# module.net
KiCad netlist of a schematic drawn in EAGLE
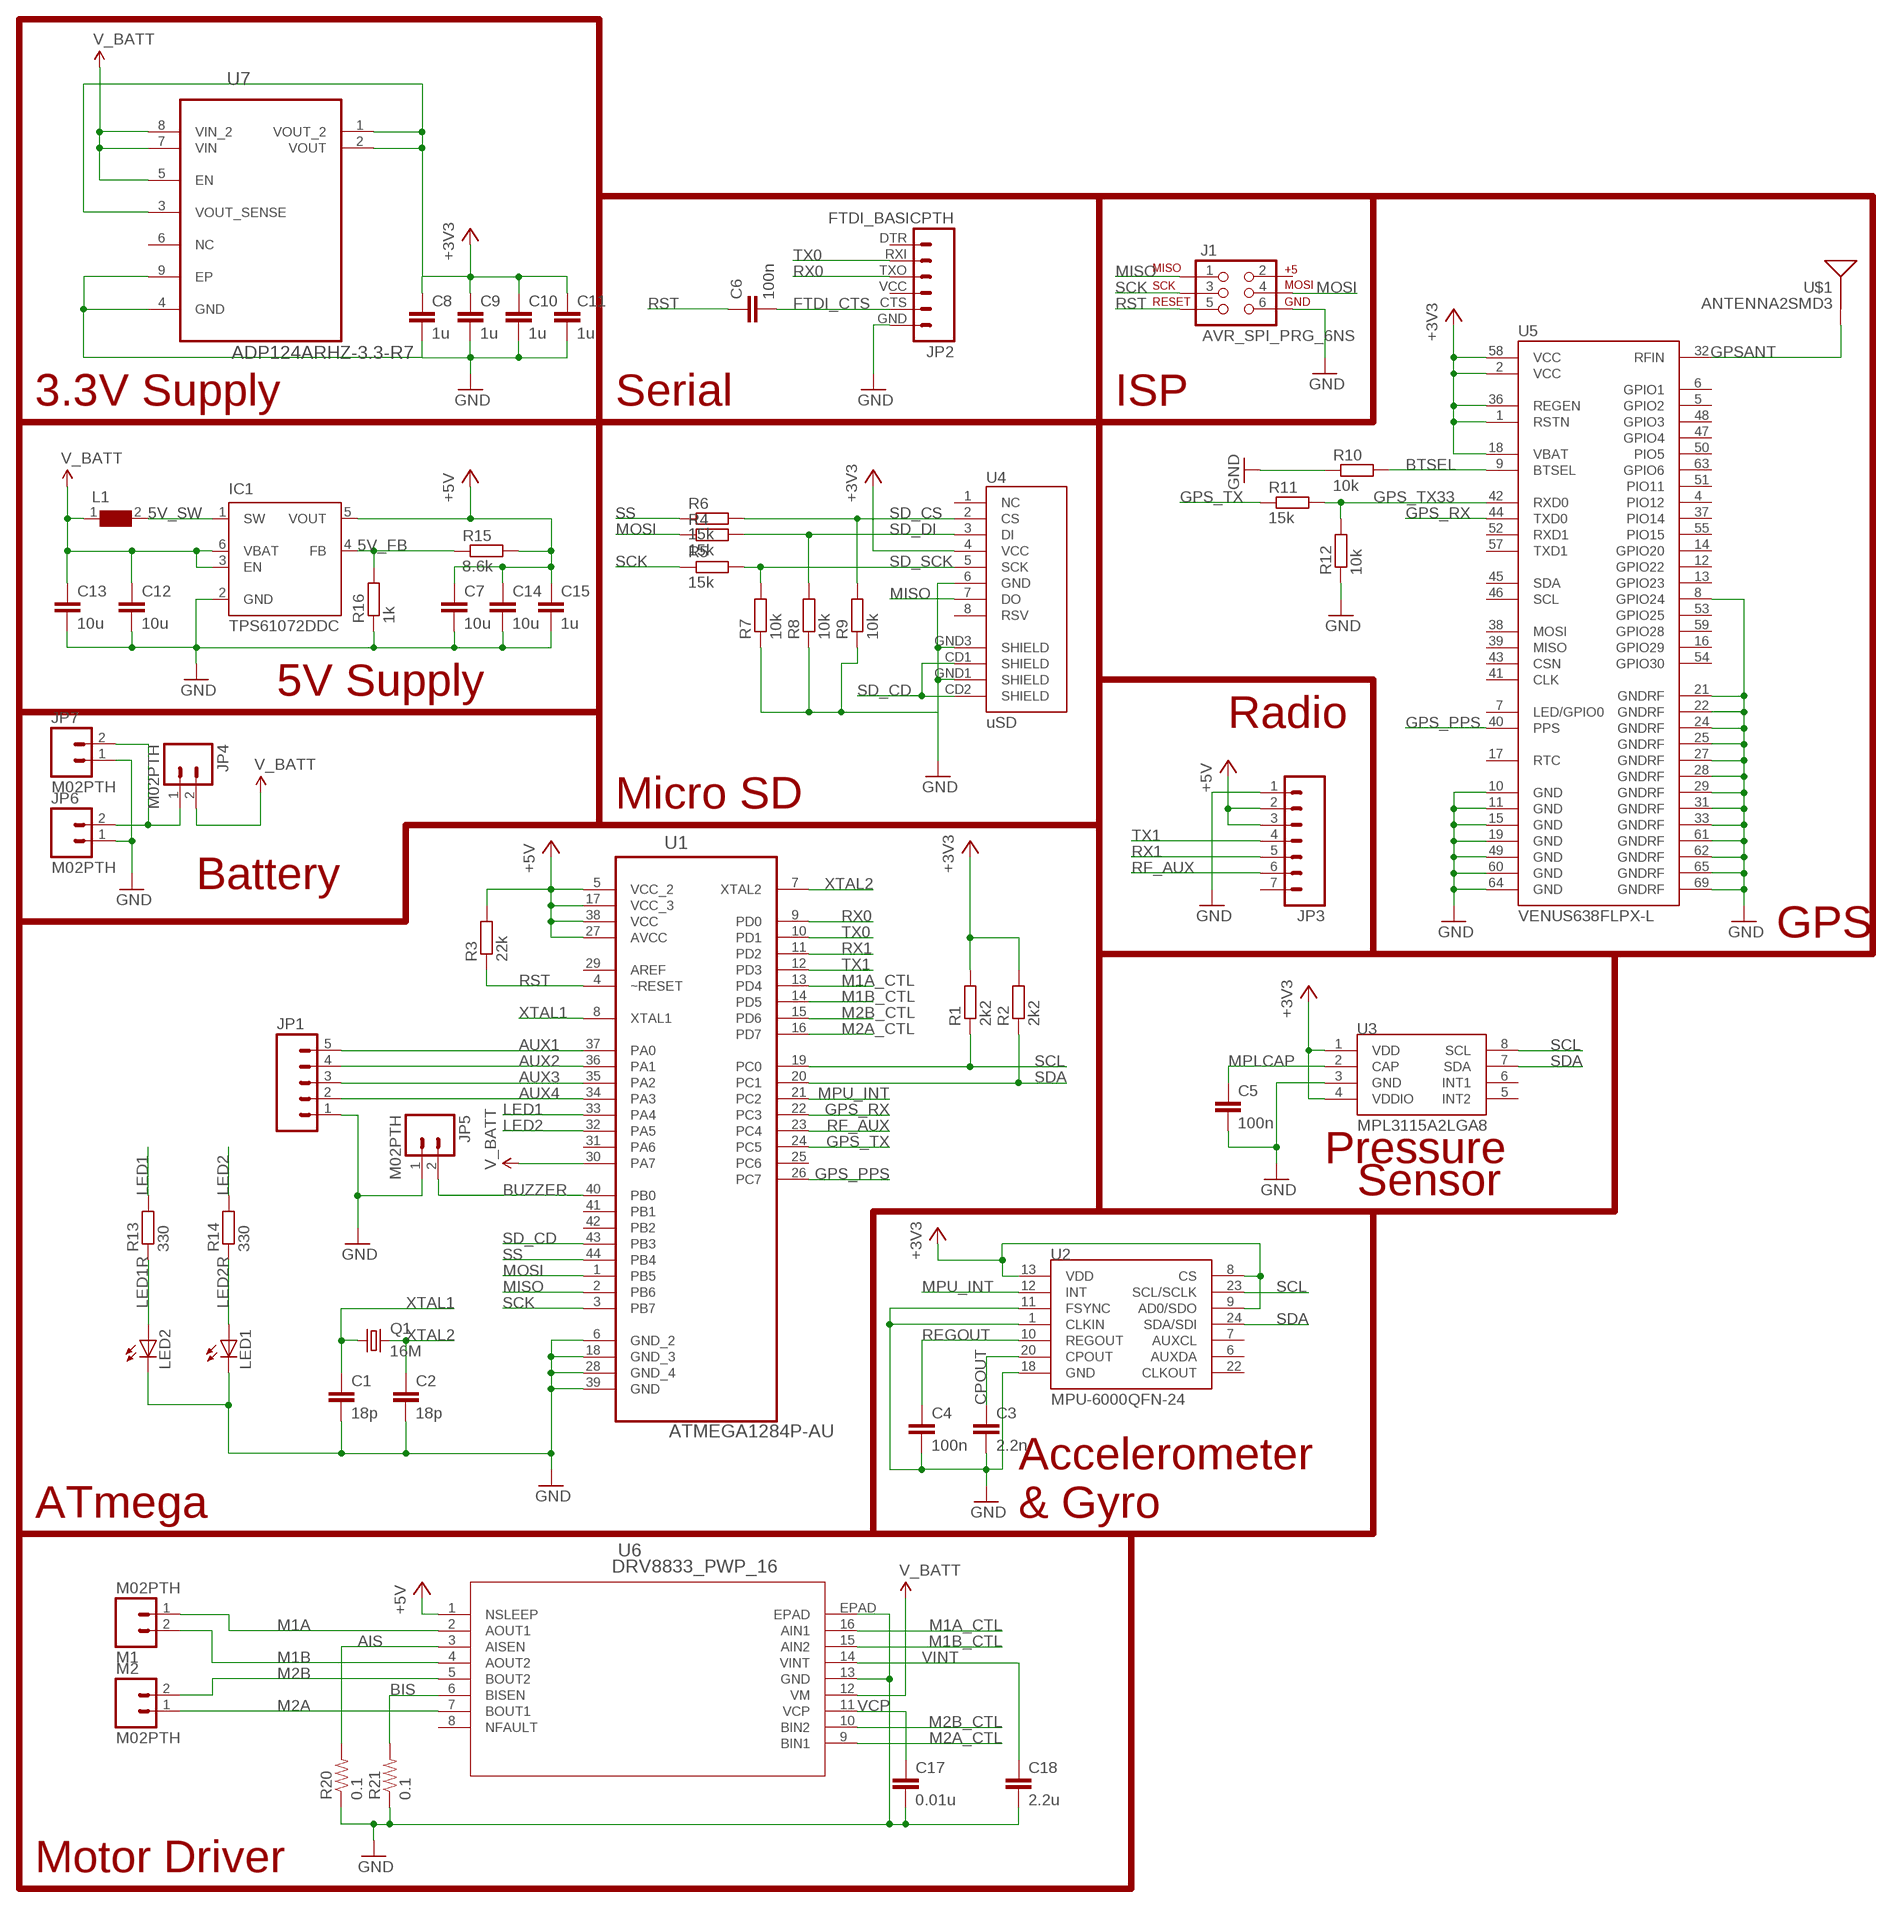
[diagram p0: schematic, sheet 1]

(export (version "E")
  (design (tool "Eeschema 10.0.6"))
  (components
    (comp (ref "C1")
      (value "18p")
      (footprint "eagle-import:C0805")
      (libsource (lib "eagle-import") (part "C-EUC0805"))
    )
    (comp (ref "C2")
      (value "18p")
      (footprint "eagle-import:C0805")
      (libsource (lib "eagle-import") (part "C-EUC0805"))
    )
    (comp (ref "C3")
      (value "2.2n")
      (footprint "eagle-import:C0805")
      (libsource (lib "eagle-import") (part "C-EUC0805"))
    )
    (comp (ref "C4")
      (value "100n")
      (footprint "eagle-import:C0805")
      (libsource (lib "eagle-import") (part "C-EUC0805"))
    )
    (comp (ref "C5")
      (value "100n")
      (footprint "eagle-import:C0805")
      (libsource (lib "eagle-import") (part "C-EUC0805"))
    )
    (comp (ref "C6")
      (value "100n")
      (footprint "eagle-import:C0805")
      (libsource (lib "eagle-import") (part "C-EUC0805"))
    )
    (comp (ref "C7")
      (value "10u")
      (footprint "eagle-import:C0805")
      (libsource (lib "eagle-import") (part "C-EUC0805"))
    )
    (comp (ref "C8")
      (value "1u")
      (footprint "eagle-import:C0603")
      (libsource (lib "eagle-import") (part "C-EUC0603"))
    )
    (comp (ref "C9")
      (value "1u")
      (footprint "eagle-import:C0603")
      (libsource (lib "eagle-import") (part "C-EUC0603"))
    )
    (comp (ref "C10")
      (value "1u")
      (footprint "eagle-import:C0603")
      (libsource (lib "eagle-import") (part "C-EUC0603"))
    )
    (comp (ref "C11")
      (value "1u")
      (footprint "eagle-import:C0603")
      (libsource (lib "eagle-import") (part "C-EUC0603"))
    )
    (comp (ref "C12")
      (value "10u")
      (footprint "eagle-import:C0805")
      (libsource (lib "eagle-import") (part "C-EUC0805"))
    )
    (comp (ref "C13")
      (value "10u")
      (footprint "eagle-import:C0805")
      (libsource (lib "eagle-import") (part "C-EUC0805"))
    )
    (comp (ref "C14")
      (value "10u")
      (footprint "eagle-import:C0805")
      (libsource (lib "eagle-import") (part "C-EUC0805"))
    )
    (comp (ref "C15")
      (value "1u")
      (footprint "eagle-import:C0805")
      (libsource (lib "eagle-import") (part "C-EUC0805"))
    )
    (comp (ref "C17")
      (value "0.01u")
      (footprint "eagle-import:0805")
      (libsource (lib "eagle-import") (part "CAP0805"))
    )
    (comp (ref "C18")
      (value "2.2u")
      (footprint "eagle-import:0805")
      (libsource (lib "eagle-import") (part "CAP0805"))
    )
    (comp (ref "IC1")
      (value "TPS61072DDC")
      (footprint "eagle-import:TSOT23-6_DDC")
      (fields (field (name "MPN") "TPS61072DDCR"))
      (libsource (lib "eagle-import") (part "TPS6107DDC2"))
    )
    (comp (ref "J1")
      (value "AVR_SPI_PRG_6NS")
      (footprint "eagle-import:2X3-NS")
      (libsource (lib "eagle-import") (part "AVR_SPI_PRG_6NS"))
    )
    (comp (ref "JP1")
      (value "M05PTH")
      (footprint "eagle-import:1X05")
      (libsource (lib "eagle-import") (part "M05PTH"))
    )
    (comp (ref "JP2")
      (value "FTDI_BASICPTH")
      (footprint "eagle-import:FTDI_BASIC")
      (libsource (lib "eagle-import") (part "FTDI_BASICPTH"))
    )
    (comp (ref "JP3")
      (value "M07")
      (footprint "eagle-import:1X07")
      (libsource (lib "eagle-import") (part "M07"))
    )
    (comp (ref "JP4")
      (value "M02PTH")
      (footprint "eagle-import:1X02")
      (libsource (lib "eagle-import") (part "M02PTH"))
    )
    (comp (ref "JP5")
      (value "M02PTH")
      (footprint "eagle-import:1X02")
      (libsource (lib "eagle-import") (part "M02PTH"))
    )
    (comp (ref "JP6")
      (value "M02PTH")
      (footprint "eagle-import:1X02")
      (libsource (lib "eagle-import") (part "M02PTH"))
    )
    (comp (ref "JP7")
      (value "M02PTH")
      (footprint "eagle-import:1X02")
      (libsource (lib "eagle-import") (part "M02PTH"))
    )
    (comp (ref "L1")
      (value "WE-TPC-744031004_3816")
      (footprint "eagle-import:WE-TPC_3816")
      (fields (field (name "MPN") "744031004 "))
      (libsource (lib "eagle-import") (part "WE-TPC_3816-744031004"))
    )
    (comp (ref "LED1")
      (value "LEDCHIPLED_0805")
      (footprint "eagle-import:CHIPLED_0805")
      (libsource (lib "eagle-import") (part "LEDCHIPLED_0805"))
    )
    (comp (ref "LED2")
      (value "LEDCHIPLED_0805")
      (footprint "eagle-import:CHIPLED_0805")
      (libsource (lib "eagle-import") (part "LEDCHIPLED_0805"))
    )
    (comp (ref "M1")
      (value "M02PTH")
      (footprint "eagle-import:1X02")
      (libsource (lib "eagle-import") (part "M02PTH"))
    )
    (comp (ref "M2")
      (value "M02PTH")
      (footprint "eagle-import:1X02")
      (libsource (lib "eagle-import") (part "M02PTH"))
    )
    (comp (ref "Q1")
      (value "16M")
      (footprint "eagle-import:HC49UP")
      (libsource (lib "eagle-import") (part "CRYSTALHC49UP"))
    )
    (comp (ref "R1")
      (value "2k2")
      (footprint "eagle-import:R0805")
      (libsource (lib "eagle-import") (part "R-EU_R0805"))
    )
    (comp (ref "R2")
      (value "2k2")
      (footprint "eagle-import:R0805")
      (libsource (lib "eagle-import") (part "R-EU_R0805"))
    )
    (comp (ref "R3")
      (value "22k")
      (footprint "eagle-import:R0805")
      (libsource (lib "eagle-import") (part "R-EU_R0805"))
    )
    (comp (ref "R4")
      (value "15k")
      (footprint "eagle-import:R0805")
      (libsource (lib "eagle-import") (part "R-EU_R0805"))
    )
    (comp (ref "R5")
      (value "15k")
      (footprint "eagle-import:R0805")
      (libsource (lib "eagle-import") (part "R-EU_R0805"))
    )
    (comp (ref "R6")
      (value "15k")
      (footprint "eagle-import:R0805")
      (libsource (lib "eagle-import") (part "R-EU_R0805"))
    )
    (comp (ref "R7")
      (value "10k")
      (footprint "eagle-import:R0805")
      (libsource (lib "eagle-import") (part "R-EU_R0805"))
    )
    (comp (ref "R8")
      (value "10k")
      (footprint "eagle-import:R0805")
      (libsource (lib "eagle-import") (part "R-EU_R0805"))
    )
    (comp (ref "R9")
      (value "10k")
      (footprint "eagle-import:R0805")
      (libsource (lib "eagle-import") (part "R-EU_R0805"))
    )
    (comp (ref "R10")
      (value "10k")
      (footprint "eagle-import:R0805")
      (libsource (lib "eagle-import") (part "R-EU_R0805"))
    )
    (comp (ref "R11")
      (value "15k")
      (footprint "eagle-import:R0805")
      (libsource (lib "eagle-import") (part "R-EU_R0805"))
    )
    (comp (ref "R12")
      (value "10k")
      (footprint "eagle-import:R0805")
      (libsource (lib "eagle-import") (part "R-EU_R0805"))
    )
    (comp (ref "R13")
      (value "330")
      (footprint "eagle-import:R0805")
      (libsource (lib "eagle-import") (part "R-EU_R0805"))
    )
    (comp (ref "R14")
      (value "330")
      (footprint "eagle-import:R0805")
      (libsource (lib "eagle-import") (part "R-EU_R0805"))
    )
    (comp (ref "R15")
      (value "8.6k")
      (footprint "eagle-import:R0805")
      (libsource (lib "eagle-import") (part "R-EU_R0805"))
    )
    (comp (ref "R16")
      (value "1k")
      (footprint "eagle-import:R0805")
      (libsource (lib "eagle-import") (part "R-EU_R0805"))
    )
    (comp (ref "R20")
      (value "0.1")
      (footprint "eagle-import:1206")
      (libsource (lib "eagle-import") (part "RESISTOR1206"))
    )
    (comp (ref "R21")
      (value "0.1")
      (footprint "eagle-import:1206")
      (libsource (lib "eagle-import") (part "RESISTOR1206"))
    )
    (comp (ref "U$1")
      (value "ANTENNA2SMD3")
      (footprint "eagle-import:ANTENNA-CHIP4")
      (libsource (lib "eagle-import") (part "ANTENNA2SMD3"))
    )
    (comp (ref "U1")
      (value "ATMEGA1284P-AU")
      (footprint "eagle-import:QFP80P1200X1200X120-44N")
      (libsource (lib "eagle-import") (part "ATMEGA1284P-AU"))
    )
    (comp (ref "U2")
      (value "MPU-6000QFN-24")
      (footprint "eagle-import:QFN-24-TESTING")
      (libsource (lib "eagle-import") (part "MPU-6000QFN-24"))
    )
    (comp (ref "U3")
      (value "MPL3115A2LGA8")
      (footprint "eagle-import:LGA8")
      (libsource (lib "eagle-import") (part "MPL3115A2LGA8"))
    )
    (comp (ref "U4")
      (value "uSD")
      (footprint "eagle-import:MICRO-SD-SOCKET-PP")
      (libsource (lib "eagle-import") (part "USD-SOCKETNEW"))
    )
    (comp (ref "U5")
      (value "VENUS638FLPX-L")
      (footprint "eagle-import:VENUS638FLPX")
      (libsource (lib "eagle-import") (part "VENUS638FLPX-L"))
    )
    (comp (ref "U6")
      (value "DRV8833_PWP_16")
      (footprint "eagle-import:PWP16_2P31X2P46")
      (fields
        (field (name "GENERIC_PART_NUMBER") "DRV8833")
        (field (name "MANUFACTURER") "Texas Instruments")
        (field (name "MANUFACTURER_PART_NUMBER") "drv8833_pwp_16")
      )
      (libsource (lib "eagle-import") (part "DRV8833_PWP_16"))
    )
    (comp (ref "U7")
      (value "ADP124ARHZ-3.3-R7")
      (footprint "eagle-import:SOP65P490X110-9N")
      (libsource (lib "eagle-import") (part "ADP124ARHZ-3.3-R7"))
    )
  )
  (nets
    (net (code "1") (name "+3V3") (class "Default")
      (node (ref "C10") (pin "1") (pinfunction "1_1") (pintype "passive"))
      (node (ref "C11") (pin "1") (pinfunction "1_1") (pintype "passive"))
      (node (ref "C8") (pin "1") (pinfunction "1_1") (pintype "passive"))
      (node (ref "C9") (pin "1") (pinfunction "1_1") (pintype "passive"))
      (node (ref "R1") (pin "2") (pinfunction "2_2") (pintype "passive"))
      (node (ref "R2") (pin "2") (pinfunction "2_2") (pintype "passive"))
      (node (ref "U2") (pin "13") (pinfunction "VDD_13") (pintype "bidirectional"))
      (node (ref "U2") (pin "8") (pinfunction "CS_8") (pintype "bidirectional"))
      (node (ref "U2") (pin "9") (pinfunction "AD0/SDO_9") (pintype "bidirectional"))
      (node (ref "U3") (pin "1") (pinfunction "VDD_1") (pintype "bidirectional"))
      (node (ref "U3") (pin "4") (pinfunction "VDDIO_4") (pintype "bidirectional"))
      (node (ref "U4") (pin "4") (pinfunction "VCC_4") (pintype "bidirectional"))
      (node (ref "U5") (pin "1") (pinfunction "RSTN_1") (pintype "bidirectional"))
      (node (ref "U5") (pin "18") (pinfunction "VBAT_18") (pintype "bidirectional"))
      (node (ref "U5") (pin "2") (pinfunction "VCC_2") (pintype "bidirectional"))
      (node (ref "U5") (pin "36") (pinfunction "REGEN_36") (pintype "bidirectional"))
      (node (ref "U5") (pin "58") (pinfunction "VCC_58") (pintype "bidirectional"))
      (node (ref "U7") (pin "1") (pinfunction "VOUT_2_1") (pintype "output"))
      (node (ref "U7") (pin "2") (pinfunction "VOUT_2") (pintype "output"))
      (node (ref "U7") (pin "3") (pinfunction "VOUT_SENSE_3") (pintype "input"))
    )
    (net (code "2") (name "+5V") (class "Default")
      (node (ref "C14") (pin "1") (pinfunction "1_1") (pintype "passive"))
      (node (ref "C15") (pin "1") (pinfunction "1_1") (pintype "passive"))
      (node (ref "C7") (pin "1") (pinfunction "1_1") (pintype "passive"))
      (node (ref "IC1") (pin "5") (pinfunction "VOUT_5") (pintype "passive"))
      (node (ref "JP3") (pin "2") (pinfunction "2_2") (pintype "passive"))
      (node (ref "JP3") (pin "3") (pinfunction "3_3") (pintype "passive"))
      (node (ref "R15") (pin "2") (pinfunction "2_2") (pintype "passive"))
      (node (ref "R3") (pin "2") (pinfunction "2_2") (pintype "passive"))
      (node (ref "U1") (pin "17") (pinfunction "VCC_3_17") (pintype "power_in"))
      (node (ref "U1") (pin "27") (pinfunction "AVCC_27") (pintype "power_in"))
      (node (ref "U1") (pin "38") (pinfunction "VCC_38") (pintype "power_in"))
      (node (ref "U1") (pin "5") (pinfunction "VCC_2_5") (pintype "power_in"))
      (node (ref "U6") (pin "1") (pinfunction "NSLEEP_1") (pintype "input"))
    )
    (net (code "3") (name "/5V_FB") (class "Default")
      (node (ref "IC1") (pin "4") (pinfunction "FB_4") (pintype "input"))
      (node (ref "R15") (pin "1") (pinfunction "1_1") (pintype "passive"))
      (node (ref "R16") (pin "2") (pinfunction "2_2") (pintype "passive"))
    )
    (net (code "4") (name "/5V_SW") (class "Default")
      (node (ref "IC1") (pin "1") (pinfunction "SW_1") (pintype "input"))
      (node (ref "L1") (pin "2") (pinfunction "2_2") (pintype "passive"))
    )
    (net (code "5") (name "/AIS") (class "Default")
      (node (ref "R20") (pin "2") (pinfunction "2_2") (pintype "passive"))
      (node (ref "U6") (pin "3") (pinfunction "AISEN_3") (pintype "bidirectional"))
    )
    (net (code "6") (name "/AUX1") (class "Default")
      (node (ref "JP1") (pin "5") (pinfunction "5_5") (pintype "passive"))
      (node (ref "U1") (pin "37") (pinfunction "PA0_37") (pintype "bidirectional"))
    )
    (net (code "7") (name "/AUX2") (class "Default")
      (node (ref "JP1") (pin "4") (pinfunction "4_4") (pintype "passive"))
      (node (ref "U1") (pin "36") (pinfunction "PA1_36") (pintype "bidirectional"))
    )
    (net (code "8") (name "/AUX3") (class "Default")
      (node (ref "JP1") (pin "3") (pinfunction "3_3") (pintype "passive"))
      (node (ref "U1") (pin "35") (pinfunction "PA2_35") (pintype "bidirectional"))
    )
    (net (code "9") (name "/AUX4") (class "Default")
      (node (ref "JP1") (pin "2") (pinfunction "2_2") (pintype "passive"))
      (node (ref "U1") (pin "34") (pinfunction "PA3_34") (pintype "bidirectional"))
    )
    (net (code "10") (name "/BIS") (class "Default")
      (node (ref "R21") (pin "2") (pinfunction "2_2") (pintype "passive"))
      (node (ref "U6") (pin "6") (pinfunction "BISEN_6") (pintype "bidirectional"))
    )
    (net (code "11") (name "/BTSEL") (class "Default")
      (node (ref "R10") (pin "2") (pinfunction "2_2") (pintype "passive"))
      (node (ref "U5") (pin "9") (pinfunction "BTSEL_9") (pintype "bidirectional"))
    )
    (net (code "12") (name "/BUZZER") (class "Default")
      (node (ref "JP5") (pin "2") (pinfunction "2_2") (pintype "passive"))
      (node (ref "U1") (pin "40") (pinfunction "PB0_40") (pintype "bidirectional"))
    )
    (net (code "13") (name "/CPOUT") (class "Default")
      (node (ref "C3") (pin "1") (pinfunction "1_1") (pintype "passive"))
      (node (ref "U2") (pin "20") (pinfunction "CPOUT_20") (pintype "bidirectional"))
    )
    (net (code "14") (name "/FTDI_CTS") (class "Default")
      (node (ref "C6") (pin "2") (pinfunction "2_2") (pintype "passive"))
      (node (ref "JP2") (pin "CTS") (pinfunction "5_CTS") (pintype "passive"))
    )
    (net (code "15") (name "/GPSANT") (class "Default")
      (node (ref "U$1") (pin "SIG") (pinfunction "SIGNAL_SIG") (pintype "bidirectional"))
      (node (ref "U5") (pin "32") (pinfunction "RFIN_32") (pintype "bidirectional"))
    )
    (net (code "16") (name "/GPS_PPS") (class "Default")
      (node (ref "U1") (pin "26") (pinfunction "PC7_26") (pintype "bidirectional"))
      (node (ref "U5") (pin "40") (pinfunction "PPS_40") (pintype "bidirectional"))
    )
    (net (code "17") (name "/GPS_RX") (class "Default")
      (node (ref "U1") (pin "22") (pinfunction "PC3_22") (pintype "bidirectional"))
      (node (ref "U5") (pin "44") (pinfunction "TXD0_44") (pintype "bidirectional"))
    )
    (net (code "18") (name "/GPS_TX") (class "Default")
      (node (ref "R11") (pin "1") (pinfunction "1_1") (pintype "passive"))
      (node (ref "U1") (pin "24") (pinfunction "PC5_24") (pintype "bidirectional"))
    )
    (net (code "19") (name "/GPS_TX33") (class "Default")
      (node (ref "R11") (pin "2") (pinfunction "2_2") (pintype "passive"))
      (node (ref "R12") (pin "2") (pinfunction "2_2") (pintype "passive"))
      (node (ref "U5") (pin "42") (pinfunction "RXD0_42") (pintype "bidirectional"))
    )
    (net (code "20") (name "/LED1") (class "Default")
      (node (ref "R13") (pin "2") (pinfunction "2_2") (pintype "passive"))
      (node (ref "U1") (pin "33") (pinfunction "PA4_33") (pintype "bidirectional"))
    )
    (net (code "21") (name "/LED1R") (class "Default")
      (node (ref "LED2") (pin "A") (pinfunction "A_A") (pintype "passive"))
      (node (ref "R13") (pin "1") (pinfunction "1_1") (pintype "passive"))
    )
    (net (code "22") (name "/LED2") (class "Default")
      (node (ref "R14") (pin "2") (pinfunction "2_2") (pintype "passive"))
      (node (ref "U1") (pin "32") (pinfunction "PA5_32") (pintype "bidirectional"))
    )
    (net (code "23") (name "/LED2R") (class "Default")
      (node (ref "LED1") (pin "A") (pinfunction "A_A") (pintype "passive"))
      (node (ref "R14") (pin "1") (pinfunction "1_1") (pintype "passive"))
    )
    (net (code "24") (name "/M1A") (class "Default")
      (node (ref "M1") (pin "1") (pinfunction "1_1") (pintype "passive"))
      (node (ref "U6") (pin "2") (pinfunction "AOUT1_2") (pintype "output"))
    )
    (net (code "25") (name "/M1A_CTL") (class "Default")
      (node (ref "U1") (pin "13") (pinfunction "PD4_13") (pintype "bidirectional"))
      (node (ref "U6") (pin "16") (pinfunction "AIN1_16") (pintype "input"))
    )
    (net (code "26") (name "/M1B") (class "Default")
      (node (ref "M1") (pin "2") (pinfunction "2_2") (pintype "passive"))
      (node (ref "U6") (pin "4") (pinfunction "AOUT2_4") (pintype "output"))
    )
    (net (code "27") (name "/M1B_CTL") (class "Default")
      (node (ref "U1") (pin "14") (pinfunction "PD5_14") (pintype "bidirectional"))
      (node (ref "U6") (pin "15") (pinfunction "AIN2_15") (pintype "input"))
    )
    (net (code "28") (name "/M2A") (class "Default")
      (node (ref "M2") (pin "1") (pinfunction "1_1") (pintype "passive"))
      (node (ref "U6") (pin "7") (pinfunction "BOUT1_7") (pintype "output"))
    )
    (net (code "29") (name "/M2A_CTL") (class "Default")
      (node (ref "U1") (pin "16") (pinfunction "PD7_16") (pintype "bidirectional"))
      (node (ref "U6") (pin "9") (pinfunction "BIN1_9") (pintype "input"))
    )
    (net (code "30") (name "/M2B") (class "Default")
      (node (ref "M2") (pin "2") (pinfunction "2_2") (pintype "passive"))
      (node (ref "U6") (pin "5") (pinfunction "BOUT2_5") (pintype "output"))
    )
    (net (code "31") (name "/M2B_CTL") (class "Default")
      (node (ref "U1") (pin "15") (pinfunction "PD6_15") (pintype "bidirectional"))
      (node (ref "U6") (pin "10") (pinfunction "BIN2_10") (pintype "input"))
    )
    (net (code "32") (name "/MISO") (class "Default")
      (node (ref "J1") (pin "1") (pinfunction "1_1") (pintype "passive"))
      (node (ref "U1") (pin "2") (pinfunction "PB6_2") (pintype "bidirectional"))
      (node (ref "U4") (pin "7") (pinfunction "DO_7") (pintype "bidirectional"))
    )
    (net (code "33") (name "/MOSI") (class "Default")
      (node (ref "J1") (pin "4") (pinfunction "4_4") (pintype "passive"))
      (node (ref "R4") (pin "1") (pinfunction "1_1") (pintype "passive"))
      (node (ref "U1") (pin "1") (pinfunction "PB5_1") (pintype "bidirectional"))
    )
    (net (code "34") (name "/MPLCAP") (class "Default")
      (node (ref "C5") (pin "1") (pinfunction "1_1") (pintype "passive"))
      (node (ref "U3") (pin "2") (pinfunction "CAP_2") (pintype "bidirectional"))
    )
    (net (code "35") (name "/MPU_INT") (class "Default")
      (node (ref "U1") (pin "21") (pinfunction "PC2_21") (pintype "bidirectional"))
      (node (ref "U2") (pin "12") (pinfunction "INT_12") (pintype "bidirectional"))
    )
    (net (code "36") (name "/REGOUT") (class "Default")
      (node (ref "C4") (pin "1") (pinfunction "1_1") (pintype "passive"))
      (node (ref "U2") (pin "10") (pinfunction "REGOUT_10") (pintype "bidirectional"))
    )
    (net (code "37") (name "/RF_AUX") (class "Default")
      (node (ref "JP3") (pin "6") (pinfunction "6_6") (pintype "passive"))
      (node (ref "U1") (pin "23") (pinfunction "PC4_23") (pintype "bidirectional"))
    )
    (net (code "38") (name "/RST") (class "Default")
      (node (ref "C6") (pin "1") (pinfunction "1_1") (pintype "passive"))
      (node (ref "J1") (pin "5") (pinfunction "5_5") (pintype "passive"))
      (node (ref "R3") (pin "1") (pinfunction "1_1") (pintype "passive"))
      (node (ref "U1") (pin "4") (pinfunction "~{RESET}_4") (pintype "input"))
    )
    (net (code "39") (name "/RX0") (class "Default")
      (node (ref "JP2") (pin "TXO") (pinfunction "3_TXO") (pintype "passive"))
      (node (ref "U1") (pin "9") (pinfunction "PD0_9") (pintype "bidirectional"))
    )
    (net (code "40") (name "/RX1") (class "Default")
      (node (ref "JP3") (pin "5") (pinfunction "5_5") (pintype "passive"))
      (node (ref "U1") (pin "11") (pinfunction "PD2_11") (pintype "bidirectional"))
    )
    (net (code "41") (name "/SCK") (class "Default")
      (node (ref "J1") (pin "3") (pinfunction "3_3") (pintype "passive"))
      (node (ref "R5") (pin "1") (pinfunction "1_1") (pintype "passive"))
      (node (ref "U1") (pin "3") (pinfunction "PB7_3") (pintype "bidirectional"))
    )
    (net (code "42") (name "/SCL") (class "Default")
      (node (ref "R1") (pin "1") (pinfunction "1_1") (pintype "passive"))
      (node (ref "U1") (pin "19") (pinfunction "PC0_19") (pintype "bidirectional"))
      (node (ref "U2") (pin "23") (pinfunction "SCL/SCLK_23") (pintype "bidirectional"))
      (node (ref "U3") (pin "8") (pinfunction "SCL_8") (pintype "bidirectional"))
    )
    (net (code "43") (name "/SDA") (class "Default")
      (node (ref "R2") (pin "1") (pinfunction "1_1") (pintype "passive"))
      (node (ref "U1") (pin "20") (pinfunction "PC1_20") (pintype "bidirectional"))
      (node (ref "U2") (pin "24") (pinfunction "SDA/SDI_24") (pintype "bidirectional"))
      (node (ref "U3") (pin "7") (pinfunction "SDA_7") (pintype "bidirectional"))
    )
    (net (code "44") (name "/SD_CD") (class "Default")
      (node (ref "U1") (pin "43") (pinfunction "PB3_43") (pintype "bidirectional"))
      (node (ref "U4") (pin "CD1") (pinfunction "SHIELD_CD1") (pintype "bidirectional"))
      (node (ref "U4") (pin "CD2") (pinfunction "SHIELD_CD2") (pintype "bidirectional"))
    )
    (net (code "45") (name "/SD_CS") (class "Default")
      (node (ref "R6") (pin "2") (pinfunction "2_2") (pintype "passive"))
      (node (ref "R9") (pin "2") (pinfunction "2_2") (pintype "passive"))
      (node (ref "U4") (pin "2") (pinfunction "CS_2") (pintype "bidirectional"))
    )
    (net (code "46") (name "/SD_DI") (class "Default")
      (node (ref "R4") (pin "2") (pinfunction "2_2") (pintype "passive"))
      (node (ref "R8") (pin "2") (pinfunction "2_2") (pintype "passive"))
      (node (ref "U4") (pin "3") (pinfunction "DI_3") (pintype "bidirectional"))
    )
    (net (code "47") (name "/SD_SCK") (class "Default")
      (node (ref "R5") (pin "2") (pinfunction "2_2") (pintype "passive"))
      (node (ref "R7") (pin "2") (pinfunction "2_2") (pintype "passive"))
      (node (ref "U4") (pin "5") (pinfunction "SCK_5") (pintype "bidirectional"))
    )
    (net (code "48") (name "/SS") (class "Default")
      (node (ref "R6") (pin "1") (pinfunction "1_1") (pintype "passive"))
      (node (ref "U1") (pin "44") (pinfunction "PB4_44") (pintype "bidirectional"))
    )
    (net (code "49") (name "/TX0") (class "Default")
      (node (ref "JP2") (pin "RXI") (pinfunction "2_RXI") (pintype "passive"))
      (node (ref "U1") (pin "10") (pinfunction "PD1_10") (pintype "bidirectional"))
    )
    (net (code "50") (name "/TX1") (class "Default")
      (node (ref "JP3") (pin "4") (pinfunction "4_4") (pintype "passive"))
      (node (ref "U1") (pin "12") (pinfunction "PD3_12") (pintype "bidirectional"))
    )
    (net (code "51") (name "/VCP") (class "Default")
      (node (ref "C17") (pin "1") (pinfunction "1_1") (pintype "passive"))
      (node (ref "U6") (pin "11") (pinfunction "VCP_11") (pintype "bidirectional"))
    )
    (net (code "52") (name "/VINT") (class "Default")
      (node (ref "C18") (pin "1") (pinfunction "1_1") (pintype "passive"))
      (node (ref "U6") (pin "14") (pinfunction "VINT_14") (pintype "power_in"))
    )
    (net (code "53") (name "/XTAL1") (class "Default")
      (node (ref "C1") (pin "1") (pinfunction "1_1") (pintype "passive"))
      (node (ref "Q1") (pin "1") (pinfunction "1_1") (pintype "passive"))
      (node (ref "U1") (pin "8") (pinfunction "XTAL1_8") (pintype "input"))
    )
    (net (code "54") (name "/XTAL2") (class "Default")
      (node (ref "C2") (pin "1") (pinfunction "1_1") (pintype "passive"))
      (node (ref "Q1") (pin "2") (pinfunction "2_2") (pintype "passive"))
      (node (ref "U1") (pin "7") (pinfunction "XTAL2_7") (pintype "output"))
    )
    (net (code "55") (name "GND") (class "Default")
      (node (ref "C1") (pin "2") (pinfunction "2_2") (pintype "passive"))
      (node (ref "C10") (pin "2") (pinfunction "2_2") (pintype "passive"))
      (node (ref "C11") (pin "2") (pinfunction "2_2") (pintype "passive"))
      (node (ref "C12") (pin "2") (pinfunction "2_2") (pintype "passive"))
      (node (ref "C13") (pin "2") (pinfunction "2_2") (pintype "passive"))
      (node (ref "C14") (pin "2") (pinfunction "2_2") (pintype "passive"))
      (node (ref "C15") (pin "2") (pinfunction "2_2") (pintype "passive"))
      (node (ref "C17") (pin "2") (pinfunction "2_2") (pintype "passive"))
      (node (ref "C18") (pin "2") (pinfunction "2_2") (pintype "passive"))
      (node (ref "C2") (pin "2") (pinfunction "2_2") (pintype "passive"))
      (node (ref "C3") (pin "2") (pinfunction "2_2") (pintype "passive"))
      (node (ref "C4") (pin "2") (pinfunction "2_2") (pintype "passive"))
      (node (ref "C5") (pin "2") (pinfunction "2_2") (pintype "passive"))
      (node (ref "C7") (pin "2") (pinfunction "2_2") (pintype "passive"))
      (node (ref "C8") (pin "2") (pinfunction "2_2") (pintype "passive"))
      (node (ref "C9") (pin "2") (pinfunction "2_2") (pintype "passive"))
      (node (ref "IC1") (pin "2") (pinfunction "GND_2") (pintype "power_in"))
      (node (ref "J1") (pin "6") (pinfunction "6_6") (pintype "passive"))
      (node (ref "JP1") (pin "1") (pinfunction "1_1") (pintype "passive"))
      (node (ref "JP2") (pin "GND") (pinfunction "6_GND") (pintype "passive"))
      (node (ref "JP3") (pin "1") (pinfunction "1_1") (pintype "passive"))
      (node (ref "JP5") (pin "1") (pinfunction "1_1") (pintype "passive"))
      (node (ref "JP6") (pin "1") (pinfunction "1_1") (pintype "passive"))
      (node (ref "JP7") (pin "1") (pinfunction "1_1") (pintype "passive"))
      (node (ref "LED1") (pin "C") (pinfunction "C_C") (pintype "passive"))
      (node (ref "LED2") (pin "C") (pinfunction "C_C") (pintype "passive"))
      (node (ref "R10") (pin "1") (pinfunction "1_1") (pintype "passive"))
      (node (ref "R12") (pin "1") (pinfunction "1_1") (pintype "passive"))
      (node (ref "R16") (pin "1") (pinfunction "1_1") (pintype "passive"))
      (node (ref "R20") (pin "1") (pinfunction "1_1") (pintype "passive"))
      (node (ref "R21") (pin "1") (pinfunction "1_1") (pintype "passive"))
      (node (ref "R7") (pin "1") (pinfunction "1_1") (pintype "passive"))
      (node (ref "R8") (pin "1") (pinfunction "1_1") (pintype "passive"))
      (node (ref "R9") (pin "1") (pinfunction "1_1") (pintype "passive"))
      (node (ref "U1") (pin "18") (pinfunction "GND_3_18") (pintype "passive"))
      (node (ref "U1") (pin "28") (pinfunction "GND_4_28") (pintype "passive"))
      (node (ref "U1") (pin "39") (pinfunction "GND_39") (pintype "passive"))
      (node (ref "U1") (pin "6") (pinfunction "GND_2_6") (pintype "passive"))
      (node (ref "U2") (pin "1") (pinfunction "CLKIN_1") (pintype "bidirectional"))
      (node (ref "U2") (pin "11") (pinfunction "FSYNC_11") (pintype "bidirectional"))
      (node (ref "U2") (pin "18") (pinfunction "GND_18") (pintype "bidirectional"))
      (node (ref "U3") (pin "3") (pinfunction "GND_3") (pintype "bidirectional"))
      (node (ref "U4") (pin "6") (pinfunction "GND_6") (pintype "bidirectional"))
      (node (ref "U4") (pin "GND1") (pinfunction "SHIELD_GND1") (pintype "bidirectional"))
      (node (ref "U4") (pin "GND3") (pinfunction "SHIELD_GND3") (pintype "bidirectional"))
      (node (ref "U5") (pin "10") (pinfunction "GND_10") (pintype "bidirectional"))
      (node (ref "U5") (pin "11") (pinfunction "GND_11") (pintype "bidirectional"))
      (node (ref "U5") (pin "15") (pinfunction "GND_15") (pintype "bidirectional"))
      (node (ref "U5") (pin "19") (pinfunction "GND_19") (pintype "bidirectional"))
      (node (ref "U5") (pin "21") (pinfunction "GNDRF_21") (pintype "bidirectional"))
      (node (ref "U5") (pin "22") (pinfunction "GNDRF_22") (pintype "bidirectional"))
      (node (ref "U5") (pin "24") (pinfunction "GNDRF_24") (pintype "bidirectional"))
      (node (ref "U5") (pin "25") (pinfunction "GNDRF_25") (pintype "bidirectional"))
      (node (ref "U5") (pin "27") (pinfunction "GNDRF_27") (pintype "bidirectional"))
      (node (ref "U5") (pin "28") (pinfunction "GNDRF_28") (pintype "bidirectional"))
      (node (ref "U5") (pin "29") (pinfunction "GNDRF_29") (pintype "bidirectional"))
      (node (ref "U5") (pin "31") (pinfunction "GNDRF_31") (pintype "bidirectional"))
      (node (ref "U5") (pin "33") (pinfunction "GNDRF_33") (pintype "bidirectional"))
      (node (ref "U5") (pin "49") (pinfunction "GND_49") (pintype "bidirectional"))
      (node (ref "U5") (pin "60") (pinfunction "GND_60") (pintype "bidirectional"))
      (node (ref "U5") (pin "61") (pinfunction "GNDRF_61") (pintype "bidirectional"))
      (node (ref "U5") (pin "62") (pinfunction "GNDRF_62") (pintype "bidirectional"))
      (node (ref "U5") (pin "64") (pinfunction "GND_64") (pintype "bidirectional"))
      (node (ref "U5") (pin "65") (pinfunction "GNDRF_65") (pintype "bidirectional"))
      (node (ref "U5") (pin "69") (pinfunction "GNDRF_69") (pintype "bidirectional"))
      (node (ref "U5") (pin "8") (pinfunction "GPIO24_8") (pintype "bidirectional"))
      (node (ref "U6") (pin "13") (pinfunction "GND_13") (pintype "power_in"))
      (node (ref "U6") (pin "EPAD") (pinfunction "EPAD_EPAD") (pintype "passive"))
      (node (ref "U7") (pin "4") (pinfunction "GND_4") (pintype "passive"))
      (node (ref "U7") (pin "9") (pinfunction "EP_9") (pintype "passive"))
    )
    (net (code "56") (name "Net-(JP4-Pad1)") (class "Default")
      (node (ref "JP4") (pin "1") (pinfunction "1_1") (pintype "passive"))
      (node (ref "JP6") (pin "2") (pinfunction "2_2") (pintype "passive"))
      (node (ref "JP7") (pin "2") (pinfunction "2_2") (pintype "passive"))
    )
    (net (code "57") (name "V_BATT") (class "Default")
      (node (ref "C12") (pin "1") (pinfunction "1_1") (pintype "passive"))
      (node (ref "C13") (pin "1") (pinfunction "1_1") (pintype "passive"))
      (node (ref "IC1") (pin "3") (pinfunction "EN_3") (pintype "input"))
      (node (ref "IC1") (pin "6") (pinfunction "VBAT_6") (pintype "input"))
      (node (ref "JP4") (pin "2") (pinfunction "2_2") (pintype "passive"))
      (node (ref "L1") (pin "1") (pinfunction "1_1") (pintype "passive"))
      (node (ref "U1") (pin "30") (pinfunction "PA7_30") (pintype "bidirectional"))
      (node (ref "U6") (pin "12") (pinfunction "VM_12") (pintype "power_in"))
      (node (ref "U7") (pin "5") (pinfunction "EN_5") (pintype "input"))
      (node (ref "U7") (pin "7") (pinfunction "VIN_7") (pintype "power_in"))
      (node (ref "U7") (pin "8") (pinfunction "VIN_2_8") (pintype "power_in"))
    )
    (net (code "58") (name "unconnected-(J1-Pad2)") (class "Default")
      (node (ref "J1") (pin "2") (pinfunction "2_2") (pintype "passive"))
    )
    (net (code "59") (name "unconnected-(JP2-1-PadDTR)") (class "Default")
      (node (ref "JP2") (pin "DTR") (pinfunction "1_DTR") (pintype "passive"))
    )
    (net (code "60") (name "unconnected-(JP2-4-PadVCC)") (class "Default")
      (node (ref "JP2") (pin "VCC") (pinfunction "4_VCC") (pintype "passive"))
    )
    (net (code "61") (name "unconnected-(JP3-Pad7)") (class "Default")
      (node (ref "JP3") (pin "7") (pinfunction "7_7") (pintype "passive"))
    )
    (net (code "62") (name "unconnected-(U1-AREF-Pad29)") (class "Default")
      (node (ref "U1") (pin "29") (pinfunction "AREF_29") (pintype "input"))
    )
    (net (code "63") (name "unconnected-(U1-PA6-Pad31)") (class "Default")
      (node (ref "U1") (pin "31") (pinfunction "PA6_31") (pintype "bidirectional"))
    )
    (net (code "64") (name "unconnected-(U1-PB1-Pad41)") (class "Default")
      (node (ref "U1") (pin "41") (pinfunction "PB1_41") (pintype "bidirectional"))
    )
    (net (code "65") (name "unconnected-(U1-PB2-Pad42)") (class "Default")
      (node (ref "U1") (pin "42") (pinfunction "PB2_42") (pintype "bidirectional"))
    )
    (net (code "66") (name "unconnected-(U1-PC6-Pad25)") (class "Default")
      (node (ref "U1") (pin "25") (pinfunction "PC6_25") (pintype "bidirectional"))
    )
    (net (code "67") (name "unconnected-(U2-AUXCL-Pad7)") (class "Default")
      (node (ref "U2") (pin "7") (pinfunction "AUXCL_7") (pintype "bidirectional"))
    )
    (net (code "68") (name "unconnected-(U2-AUXDA-Pad6)") (class "Default")
      (node (ref "U2") (pin "6") (pinfunction "AUXDA_6") (pintype "bidirectional"))
    )
    (net (code "69") (name "unconnected-(U2-CLKOUT-Pad22)") (class "Default")
      (node (ref "U2") (pin "22") (pinfunction "CLKOUT_22") (pintype "bidirectional"))
    )
    (net (code "70") (name "unconnected-(U3-INT1-Pad6)") (class "Default")
      (node (ref "U3") (pin "6") (pinfunction "INT1_6") (pintype "bidirectional"))
    )
    (net (code "71") (name "unconnected-(U3-INT2-Pad5)") (class "Default")
      (node (ref "U3") (pin "5") (pinfunction "INT2_5") (pintype "bidirectional"))
    )
    (net (code "72") (name "unconnected-(U4-NC-Pad1)") (class "Default")
      (node (ref "U4") (pin "1") (pinfunction "NC_1") (pintype "bidirectional"))
    )
    (net (code "73") (name "unconnected-(U4-RSV-Pad8)") (class "Default")
      (node (ref "U4") (pin "8") (pinfunction "RSV_8") (pintype "bidirectional"))
    )
    (net (code "74") (name "unconnected-(U5-CLK-Pad41)") (class "Default")
      (node (ref "U5") (pin "41") (pinfunction "CLK_41") (pintype "bidirectional"))
    )
    (net (code "75") (name "unconnected-(U5-CSN-Pad43)") (class "Default")
      (node (ref "U5") (pin "43") (pinfunction "CSN_43") (pintype "bidirectional"))
    )
    (net (code "76") (name "unconnected-(U5-GPIO1-Pad6)") (class "Default")
      (node (ref "U5") (pin "6") (pinfunction "GPIO1_6") (pintype "bidirectional"))
    )
    (net (code "77") (name "unconnected-(U5-GPIO2-Pad5)") (class "Default")
      (node (ref "U5") (pin "5") (pinfunction "GPIO2_5") (pintype "bidirectional"))
    )
    (net (code "78") (name "unconnected-(U5-GPIO3-Pad48)") (class "Default")
      (node (ref "U5") (pin "48") (pinfunction "GPIO3_48") (pintype "bidirectional"))
    )
    (net (code "79") (name "unconnected-(U5-GPIO4-Pad47)") (class "Default")
      (node (ref "U5") (pin "47") (pinfunction "GPIO4_47") (pintype "bidirectional"))
    )
    (net (code "80") (name "unconnected-(U5-GPIO6-Pad63)") (class "Default")
      (node (ref "U5") (pin "63") (pinfunction "GPIO6_63") (pintype "bidirectional"))
    )
    (net (code "81") (name "unconnected-(U5-GPIO20-Pad14)") (class "Default")
      (node (ref "U5") (pin "14") (pinfunction "GPIO20_14") (pintype "bidirectional"))
    )
    (net (code "82") (name "unconnected-(U5-GPIO22-Pad12)") (class "Default")
      (node (ref "U5") (pin "12") (pinfunction "GPIO22_12") (pintype "bidirectional"))
    )
    (net (code "83") (name "unconnected-(U5-GPIO23-Pad13)") (class "Default")
      (node (ref "U5") (pin "13") (pinfunction "GPIO23_13") (pintype "bidirectional"))
    )
    (net (code "84") (name "unconnected-(U5-GPIO25-Pad53)") (class "Default")
      (node (ref "U5") (pin "53") (pinfunction "GPIO25_53") (pintype "bidirectional"))
    )
    (net (code "85") (name "unconnected-(U5-GPIO28-Pad59)") (class "Default")
      (node (ref "U5") (pin "59") (pinfunction "GPIO28_59") (pintype "bidirectional"))
    )
    (net (code "86") (name "unconnected-(U5-GPIO29-Pad16)") (class "Default")
      (node (ref "U5") (pin "16") (pinfunction "GPIO29_16") (pintype "bidirectional"))
    )
    (net (code "87") (name "unconnected-(U5-GPIO30-Pad54)") (class "Default")
      (node (ref "U5") (pin "54") (pinfunction "GPIO30_54") (pintype "bidirectional"))
    )
    (net (code "88") (name "unconnected-(U5-LED{slash}GPIO0-Pad7)") (class "Default")
      (node (ref "U5") (pin "7") (pinfunction "LED/GPIO0_7") (pintype "bidirectional"))
    )
    (net (code "89") (name "unconnected-(U5-MISO-Pad39)") (class "Default")
      (node (ref "U5") (pin "39") (pinfunction "MISO_39") (pintype "bidirectional"))
    )
    (net (code "90") (name "unconnected-(U5-MOSI-Pad38)") (class "Default")
      (node (ref "U5") (pin "38") (pinfunction "MOSI_38") (pintype "bidirectional"))
    )
    (net (code "91") (name "unconnected-(U5-PIO5-Pad50)") (class "Default")
      (node (ref "U5") (pin "50") (pinfunction "PIO5_50") (pintype "bidirectional"))
    )
    (net (code "92") (name "unconnected-(U5-PIO11-Pad51)") (class "Default")
      (node (ref "U5") (pin "51") (pinfunction "PIO11_51") (pintype "bidirectional"))
    )
    (net (code "93") (name "unconnected-(U5-PIO12-Pad4)") (class "Default")
      (node (ref "U5") (pin "4") (pinfunction "PIO12_4") (pintype "bidirectional"))
    )
    (net (code "94") (name "unconnected-(U5-PIO14-Pad37)") (class "Default")
      (node (ref "U5") (pin "37") (pinfunction "PIO14_37") (pintype "bidirectional"))
    )
    (net (code "95") (name "unconnected-(U5-PIO15-Pad55)") (class "Default")
      (node (ref "U5") (pin "55") (pinfunction "PIO15_55") (pintype "bidirectional"))
    )
    (net (code "96") (name "unconnected-(U5-RTC-Pad17)") (class "Default")
      (node (ref "U5") (pin "17") (pinfunction "RTC_17") (pintype "bidirectional"))
    )
    (net (code "97") (name "unconnected-(U5-RXD1-Pad52)") (class "Default")
      (node (ref "U5") (pin "52") (pinfunction "RXD1_52") (pintype "bidirectional"))
    )
    (net (code "98") (name "unconnected-(U5-SCL-Pad46)") (class "Default")
      (node (ref "U5") (pin "46") (pinfunction "SCL_46") (pintype "bidirectional"))
    )
    (net (code "99") (name "unconnected-(U5-SDA-Pad45)") (class "Default")
      (node (ref "U5") (pin "45") (pinfunction "SDA_45") (pintype "bidirectional"))
    )
    (net (code "100") (name "unconnected-(U5-TXD1-Pad57)") (class "Default")
      (node (ref "U5") (pin "57") (pinfunction "TXD1_57") (pintype "bidirectional"))
    )
    (net (code "101") (name "unconnected-(U6-NFAULT-Pad8)") (class "Default")
      (node (ref "U6") (pin "8") (pinfunction "NFAULT_8") (pintype "output"))
    )
    (net (code "102") (name "unconnected-(U7-NC-Pad6)") (class "Default")
      (node (ref "U7") (pin "6") (pinfunction "NC_6") (pintype "no_connect"))
    )
  )
)
